# DB10005_BatteryStackMonitor.net
KiCad netlist of a schematic drawn in Altium Designer
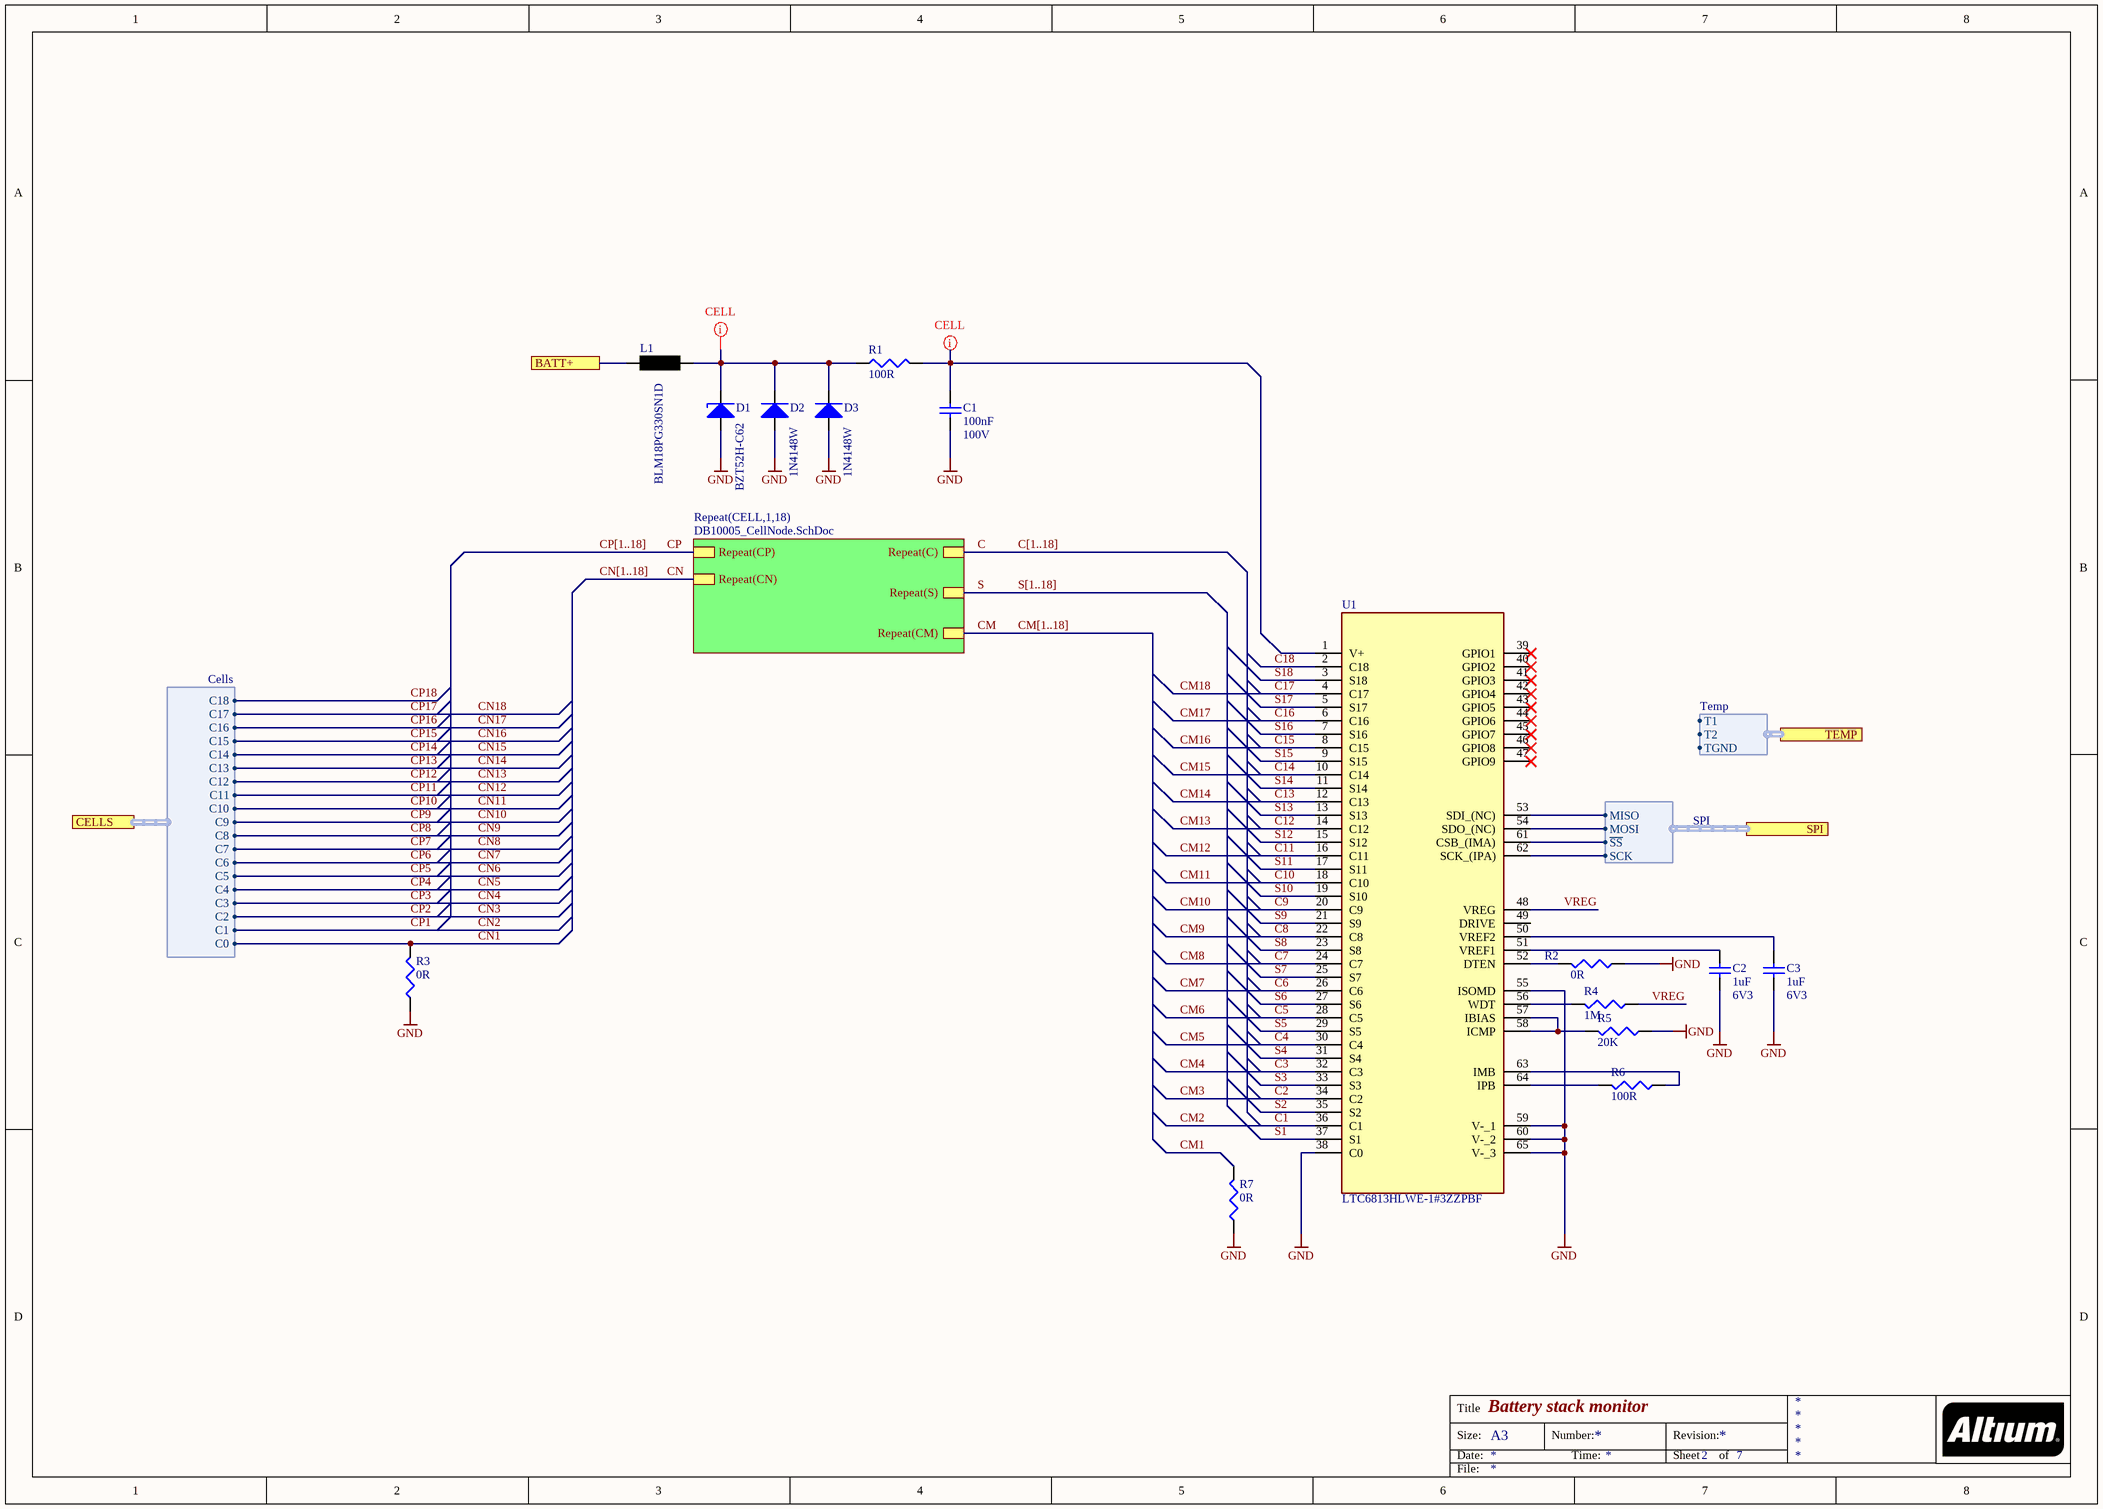
[diagram p0: DB10005_BatteryStackMonitor.SchDoc]

(export (version "E")
  (design (tool "Eeschema 10.0.6"))
  (components
    (comp (ref "C1")
      (value "100nF")
      (footprint "C-0805")
      (description "Capacitor, 100nF, 100V, X7R")
      (fields (field (name "VOLTAGE RATING") "100V"))
      (libsource (lib "AR_Capacitors_Ceramic") (part "100nF/0805/CER/100V"))
    )
    (comp (ref "C2")
      (value "1uF")
      (footprint "C0402")
      (description "Capacitor, 1uF, 6.3V, X5R")
      (fields (field (name "VOLTAGE RATING") "6V3"))
      (libsource (lib "AR_Capacitors_Ceramic") (part "1uF/0402/CER/6.3V"))
    )
    (comp (ref "C3")
      (value "1uF")
      (footprint "C0402")
      (description "Capacitor, 1uF, 6.3V, X5R")
      (fields (field (name "VOLTAGE RATING") "6V3"))
      (libsource (lib "AR_Capacitors_Ceramic") (part "1uF/0402/CER/6.3V"))
    )
    (comp (ref "D1")
      (value "BZT52H-C62")
      (footprint "SOD123W")
      (description "Diode Zener, Vz: 62V, If: 0.25A, Vf: 0.9V")
      (libsource (lib "AR_Diodes") (part "BZT52H-C62,115"))
    )
    (comp (ref "D2")
      (value "1N4148W")
      (footprint "SOD123")
      (description "Diode, Vrrm: 100V, If: 0.15A, Vf: 1V")
      (libsource (lib "AR_Diodes") (part "MMSD4148T1G"))
    )
    (comp (ref "D3")
      (value "1N4148W")
      (footprint "SOD123")
      (description "Diode, Vrrm: 100V, If: 0.15A, Vf: 1V")
      (libsource (lib "AR_Diodes") (part "MMSD4148T1G"))
    )
    (comp (ref "L1")
      (value "BLM18PG330SN1D")
      (footprint "L0603")
      (description "Ferrite Bead, Impedance:33ohm, DC Resistance Max:0.025ohm, DC Current Rating:3A")
      (libsource (lib "AR_Inductors") (part "BLM18PG330SN1D"))
    )
    (comp (ref "R1")
      (value "100R")
      (footprint "0603")
      (description "Resistor, 100R, 1%, 0.063W, 50V, 200PPM, 0603")
      (libsource (lib "AR_Resistors_SMD") (part "100/0603/0063W/50V"))
    )
    (comp (ref "R2")
      (value "0R")
      (footprint "0603")
      (description "Resistor, 0R, 0.1%, 0.063W, 50V, 200PPM, 0603")
      (libsource (lib "AR_Resistors_SMD") (part "0/0603/0063W/50V"))
    )
    (comp (ref "R3")
      (value "0R")
      (footprint "0603")
      (description "Resistor, 0R, 0.1%, 0.063W, 50V, 200PPM, 0603")
      (libsource (lib "AR_Resistors_SMD") (part "0/0603/0063W/50V"))
    )
    (comp (ref "R4")
      (value "1M")
      (footprint "0402")
      (description "Resistor, 1M, 0.1%, 0.0625W, 50V, 100PPM, 0402")
      (libsource (lib "AR_Resistors_SMD") (part "1M/0402/0063W/50V"))
    )
    (comp (ref "R5")
      (value "20K")
      (footprint "0402")
      (description "Resistor, 1M, 0.1%, 0.0625W, 50V, 100PPM, 0402")
      (libsource (lib "AR_Resistors_SMD") (part "1M/0402/0063W/50V"))
    )
    (comp (ref "R6")
      (value "100R")
      (footprint "0402")
      (description "Resistor, 1M, 0.1%, 0.0625W, 50V, 100PPM, 0402")
      (libsource (lib "AR_Resistors_SMD") (part "1M/0402/0063W/50V"))
    )
    (comp (ref "R7")
      (value "0R")
      (footprint "0603")
      (description "Resistor, 0R, 0.1%, 0.063W, 50V, 200PPM, 0603")
      (libsource (lib "AR_Resistors_SMD") (part "0/0603/0063W/50V"))
    )
    (comp (ref "U1")
      (value "LTC6813HLWE-1#3ZZPBF")
      (footprint "QFP50P1200X1200X160-65N")
      (description "Integrated Circuit")
      (fields (field (name "MOUSER PART NUMBER") "584-6813HLWE13ZZPBF"))
      (libsource (lib "DB10005_DieBieMS") (part "LTC6813HLWE-1#3ZZPBF"))
    )
  )
  (nets
    (net (code "4") (name "/BATT+") (class "Default")
      (node (ref "L1") (pin "1") (pinfunction "1_1") (pintype "passive"))
    )
    (net (code "6") (name "/C1") (class "Default")
      (node (ref "U1") (pin "36") (pinfunction "C1_36") (pintype "passive"))
    )
    (net (code "7") (name "/C2") (class "Default")
      (node (ref "U1") (pin "34") (pinfunction "C2_34") (pintype "passive"))
    )
    (net (code "8") (name "/C3") (class "Default")
      (node (ref "U1") (pin "32") (pinfunction "C3_32") (pintype "passive"))
    )
    (net (code "9") (name "/C4") (class "Default")
      (node (ref "U1") (pin "30") (pinfunction "C4_30") (pintype "passive"))
    )
    (net (code "10") (name "/C5") (class "Default")
      (node (ref "U1") (pin "28") (pinfunction "C5_28") (pintype "passive"))
    )
    (net (code "11") (name "/C6") (class "Default")
      (node (ref "U1") (pin "26") (pinfunction "C6_26") (pintype "passive"))
    )
    (net (code "12") (name "/C7") (class "Default")
      (node (ref "U1") (pin "24") (pinfunction "C7_24") (pintype "passive"))
    )
    (net (code "13") (name "/C8") (class "Default")
      (node (ref "U1") (pin "22") (pinfunction "C8_22") (pintype "passive"))
    )
    (net (code "14") (name "/C9") (class "Default")
      (node (ref "U1") (pin "20") (pinfunction "C9_20") (pintype "passive"))
    )
    (net (code "15") (name "/C10") (class "Default")
      (node (ref "U1") (pin "18") (pinfunction "C10_18") (pintype "passive"))
    )
    (net (code "16") (name "/C11") (class "Default")
      (node (ref "U1") (pin "16") (pinfunction "C11_16") (pintype "passive"))
    )
    (net (code "17") (name "/C12") (class "Default")
      (node (ref "U1") (pin "14") (pinfunction "C12_14") (pintype "passive"))
    )
    (net (code "18") (name "/C13") (class "Default")
      (node (ref "U1") (pin "12") (pinfunction "C13_12") (pintype "passive"))
    )
    (net (code "19") (name "/C14") (class "Default")
      (node (ref "U1") (pin "10") (pinfunction "C14_10") (pintype "passive"))
    )
    (net (code "20") (name "/C15") (class "Default")
      (node (ref "U1") (pin "8") (pinfunction "C15_8") (pintype "passive"))
    )
    (net (code "21") (name "/C16") (class "Default")
      (node (ref "U1") (pin "6") (pinfunction "C16_6") (pintype "passive"))
    )
    (net (code "22") (name "/C17") (class "Default")
      (node (ref "U1") (pin "4") (pinfunction "C17_4") (pintype "passive"))
    )
    (net (code "23") (name "/C18") (class "Default")
      (node (ref "U1") (pin "2") (pinfunction "C18_2") (pintype "passive"))
    )
    (net (code "25") (name "/CM1") (class "Default")
      (node (ref "R7") (pin "2") (pinfunction "2_2") (pintype "passive"))
    )
    (net (code "28") (name "/CN1") (class "Default")
      (node (ref "R3") (pin "2") (pinfunction "2_2") (pintype "passive"))
    )
    (net (code "51") (name "/MISO") (class "Default")
      (node (ref "U1") (pin "53") (pinfunction "SDI_(NC)_53") (pintype "passive"))
    )
    (net (code "52") (name "/MOSI") (class "Default")
      (node (ref "U1") (pin "54") (pinfunction "SDO_(NC)_54") (pintype "passive"))
    )
    (net (code "54") (name "/S1") (class "Default")
      (node (ref "U1") (pin "37") (pinfunction "S1_37") (pintype "passive"))
    )
    (net (code "55") (name "/S2") (class "Default")
      (node (ref "U1") (pin "35") (pinfunction "S2_35") (pintype "passive"))
    )
    (net (code "56") (name "/S3") (class "Default")
      (node (ref "U1") (pin "33") (pinfunction "S3_33") (pintype "passive"))
    )
    (net (code "57") (name "/S4") (class "Default")
      (node (ref "U1") (pin "31") (pinfunction "S4_31") (pintype "passive"))
    )
    (net (code "58") (name "/S5") (class "Default")
      (node (ref "U1") (pin "29") (pinfunction "S5_29") (pintype "passive"))
    )
    (net (code "59") (name "/S6") (class "Default")
      (node (ref "U1") (pin "27") (pinfunction "S6_27") (pintype "passive"))
    )
    (net (code "60") (name "/S7") (class "Default")
      (node (ref "U1") (pin "25") (pinfunction "S7_25") (pintype "passive"))
    )
    (net (code "61") (name "/S8") (class "Default")
      (node (ref "U1") (pin "23") (pinfunction "S8_23") (pintype "passive"))
    )
    (net (code "62") (name "/S9") (class "Default")
      (node (ref "U1") (pin "21") (pinfunction "S9_21") (pintype "passive"))
    )
    (net (code "63") (name "/S10") (class "Default")
      (node (ref "U1") (pin "19") (pinfunction "S10_19") (pintype "passive"))
    )
    (net (code "64") (name "/S11") (class "Default")
      (node (ref "U1") (pin "17") (pinfunction "S11_17") (pintype "passive"))
    )
    (net (code "65") (name "/S12") (class "Default")
      (node (ref "U1") (pin "15") (pinfunction "S12_15") (pintype "passive"))
    )
    (net (code "66") (name "/S13") (class "Default")
      (node (ref "U1") (pin "13") (pinfunction "S13_13") (pintype "passive"))
    )
    (net (code "67") (name "/S14") (class "Default")
      (node (ref "U1") (pin "11") (pinfunction "S14_11") (pintype "passive"))
    )
    (net (code "68") (name "/S15") (class "Default")
      (node (ref "U1") (pin "9") (pinfunction "S15_9") (pintype "passive"))
    )
    (net (code "69") (name "/S16") (class "Default")
      (node (ref "U1") (pin "7") (pinfunction "S16_7") (pintype "passive"))
    )
    (net (code "70") (name "/S17") (class "Default")
      (node (ref "U1") (pin "5") (pinfunction "S17_5") (pintype "passive"))
    )
    (net (code "71") (name "/S18") (class "Default")
      (node (ref "U1") (pin "3") (pinfunction "S18_3") (pintype "passive"))
    )
    (net (code "72") (name "/SCK") (class "Default")
      (node (ref "U1") (pin "62") (pinfunction "SCK_(IPA)_62") (pintype "passive"))
    )
    (net (code "74") (name "/VREG") (class "Default")
      (node (ref "R4") (pin "1") (pinfunction "1_1") (pintype "passive"))
      (node (ref "U1") (pin "48") (pinfunction "VREG_48") (pintype "passive"))
    )
    (net (code "78") (name "/~{SS}") (class "Default")
      (node (ref "U1") (pin "61") (pinfunction "CSB_(IMA)_61") (pintype "passive"))
    )
    (net (code "79") (name "GND") (class "Default")
      (node (ref "C1") (pin "1") (pinfunction "1_1") (pintype "passive"))
      (node (ref "C2") (pin "2") (pinfunction "2_2") (pintype "passive"))
      (node (ref "C3") (pin "2") (pinfunction "2_2") (pintype "passive"))
      (node (ref "D1") (pin "1") (pinfunction "1_1") (pintype "passive"))
      (node (ref "D2") (pin "1") (pinfunction "A_1") (pintype "passive"))
      (node (ref "D3") (pin "1") (pinfunction "A_1") (pintype "passive"))
      (node (ref "R2") (pin "1") (pinfunction "1_1") (pintype "passive"))
      (node (ref "R3") (pin "1") (pinfunction "1_1") (pintype "passive"))
      (node (ref "R5") (pin "1") (pinfunction "1_1") (pintype "passive"))
      (node (ref "R7") (pin "1") (pinfunction "1_1") (pintype "passive"))
      (node (ref "U1") (pin "38") (pinfunction "C0_38") (pintype "passive"))
      (node (ref "U1") (pin "55") (pinfunction "ISOMD_55") (pintype "passive"))
      (node (ref "U1") (pin "59") (pinfunction "V-_1_59") (pintype "passive"))
      (node (ref "U1") (pin "60") (pinfunction "V-_2_60") (pintype "passive"))
      (node (ref "U1") (pin "65") (pinfunction "V-_3_65") (pintype "passive"))
    )
    (net (code "80") (name "Net-(D2-K)") (class "Default")
      (node (ref "D1") (pin "2") (pinfunction "2_2") (pintype "passive"))
      (node (ref "D2") (pin "2") (pinfunction "K_2") (pintype "passive"))
      (node (ref "D3") (pin "2") (pinfunction "K_2") (pintype "passive"))
      (node (ref "L1") (pin "2") (pinfunction "2_2") (pintype "passive"))
      (node (ref "R1") (pin "1") (pinfunction "1_1") (pintype "passive"))
    )
    (net (code "81") (name "Net-(U1-DTEN)") (class "Default")
      (node (ref "R2") (pin "2") (pinfunction "2_2") (pintype "passive"))
      (node (ref "U1") (pin "52") (pinfunction "DTEN_52") (pintype "passive"))
    )
    (net (code "82") (name "Net-(U1-IBIAS)") (class "Default")
      (node (ref "R5") (pin "2") (pinfunction "2_2") (pintype "passive"))
      (node (ref "U1") (pin "57") (pinfunction "IBIAS_57") (pintype "passive"))
      (node (ref "U1") (pin "58") (pinfunction "ICMP_58") (pintype "passive"))
    )
    (net (code "83") (name "Net-(U1-IMB)") (class "Default")
      (node (ref "R6") (pin "1") (pinfunction "1_1") (pintype "passive"))
      (node (ref "U1") (pin "63") (pinfunction "IMB_63") (pintype "passive"))
    )
    (net (code "84") (name "Net-(U1-IPB)") (class "Default")
      (node (ref "R6") (pin "2") (pinfunction "2_2") (pintype "passive"))
      (node (ref "U1") (pin "64") (pinfunction "IPB_64") (pintype "passive"))
    )
    (net (code "85") (name "Net-(U1-V+)") (class "Default")
      (node (ref "C1") (pin "2") (pinfunction "2_2") (pintype "passive"))
      (node (ref "R1") (pin "2") (pinfunction "2_2") (pintype "passive"))
      (node (ref "U1") (pin "1") (pinfunction "V+_1") (pintype "passive"))
    )
    (net (code "86") (name "Net-(U1-VREF1)") (class "Default")
      (node (ref "C2") (pin "1") (pinfunction "1_1") (pintype "passive"))
      (node (ref "U1") (pin "51") (pinfunction "VREF1_51") (pintype "passive"))
    )
    (net (code "87") (name "Net-(U1-VREF2)") (class "Default")
      (node (ref "C3") (pin "1") (pinfunction "1_1") (pintype "passive"))
      (node (ref "U1") (pin "50") (pinfunction "VREF2_50") (pintype "passive"))
    )
    (net (code "88") (name "Net-(U1-WDT)") (class "Default")
      (node (ref "R4") (pin "2") (pinfunction "2_2") (pintype "passive"))
      (node (ref "U1") (pin "56") (pinfunction "WDT_56") (pintype "passive"))
    )
    (net (code "89") (name "unconnected-(U1-DRIVE-Pad49)") (class "Default")
      (node (ref "U1") (pin "49") (pinfunction "DRIVE_49") (pintype "passive"))
    )
    (net (code "90") (name "unconnected-(U1-GPIO1-Pad39)") (class "Default")
      (node (ref "U1") (pin "39") (pinfunction "GPIO1_39") (pintype "passive+no_connect"))
    )
    (net (code "91") (name "unconnected-(U1-GPIO2-Pad40)") (class "Default")
      (node (ref "U1") (pin "40") (pinfunction "GPIO2_40") (pintype "passive+no_connect"))
    )
    (net (code "92") (name "unconnected-(U1-GPIO3-Pad41)") (class "Default")
      (node (ref "U1") (pin "41") (pinfunction "GPIO3_41") (pintype "passive+no_connect"))
    )
    (net (code "93") (name "unconnected-(U1-GPIO4-Pad42)") (class "Default")
      (node (ref "U1") (pin "42") (pinfunction "GPIO4_42") (pintype "passive+no_connect"))
    )
    (net (code "94") (name "unconnected-(U1-GPIO5-Pad43)") (class "Default")
      (node (ref "U1") (pin "43") (pinfunction "GPIO5_43") (pintype "passive+no_connect"))
    )
    (net (code "95") (name "unconnected-(U1-GPIO6-Pad44)") (class "Default")
      (node (ref "U1") (pin "44") (pinfunction "GPIO6_44") (pintype "passive+no_connect"))
    )
    (net (code "96") (name "unconnected-(U1-GPIO7-Pad45)") (class "Default")
      (node (ref "U1") (pin "45") (pinfunction "GPIO7_45") (pintype "passive+no_connect"))
    )
    (net (code "97") (name "unconnected-(U1-GPIO8-Pad46)") (class "Default")
      (node (ref "U1") (pin "46") (pinfunction "GPIO8_46") (pintype "passive+no_connect"))
    )
    (net (code "98") (name "unconnected-(U1-GPIO9-Pad47)") (class "Default")
      (node (ref "U1") (pin "47") (pinfunction "GPIO9_47") (pintype "passive+no_connect"))
    )
  )
)
